# Amplifier_3.net
KiCad netlist of a schematic drawn in Altium Designer
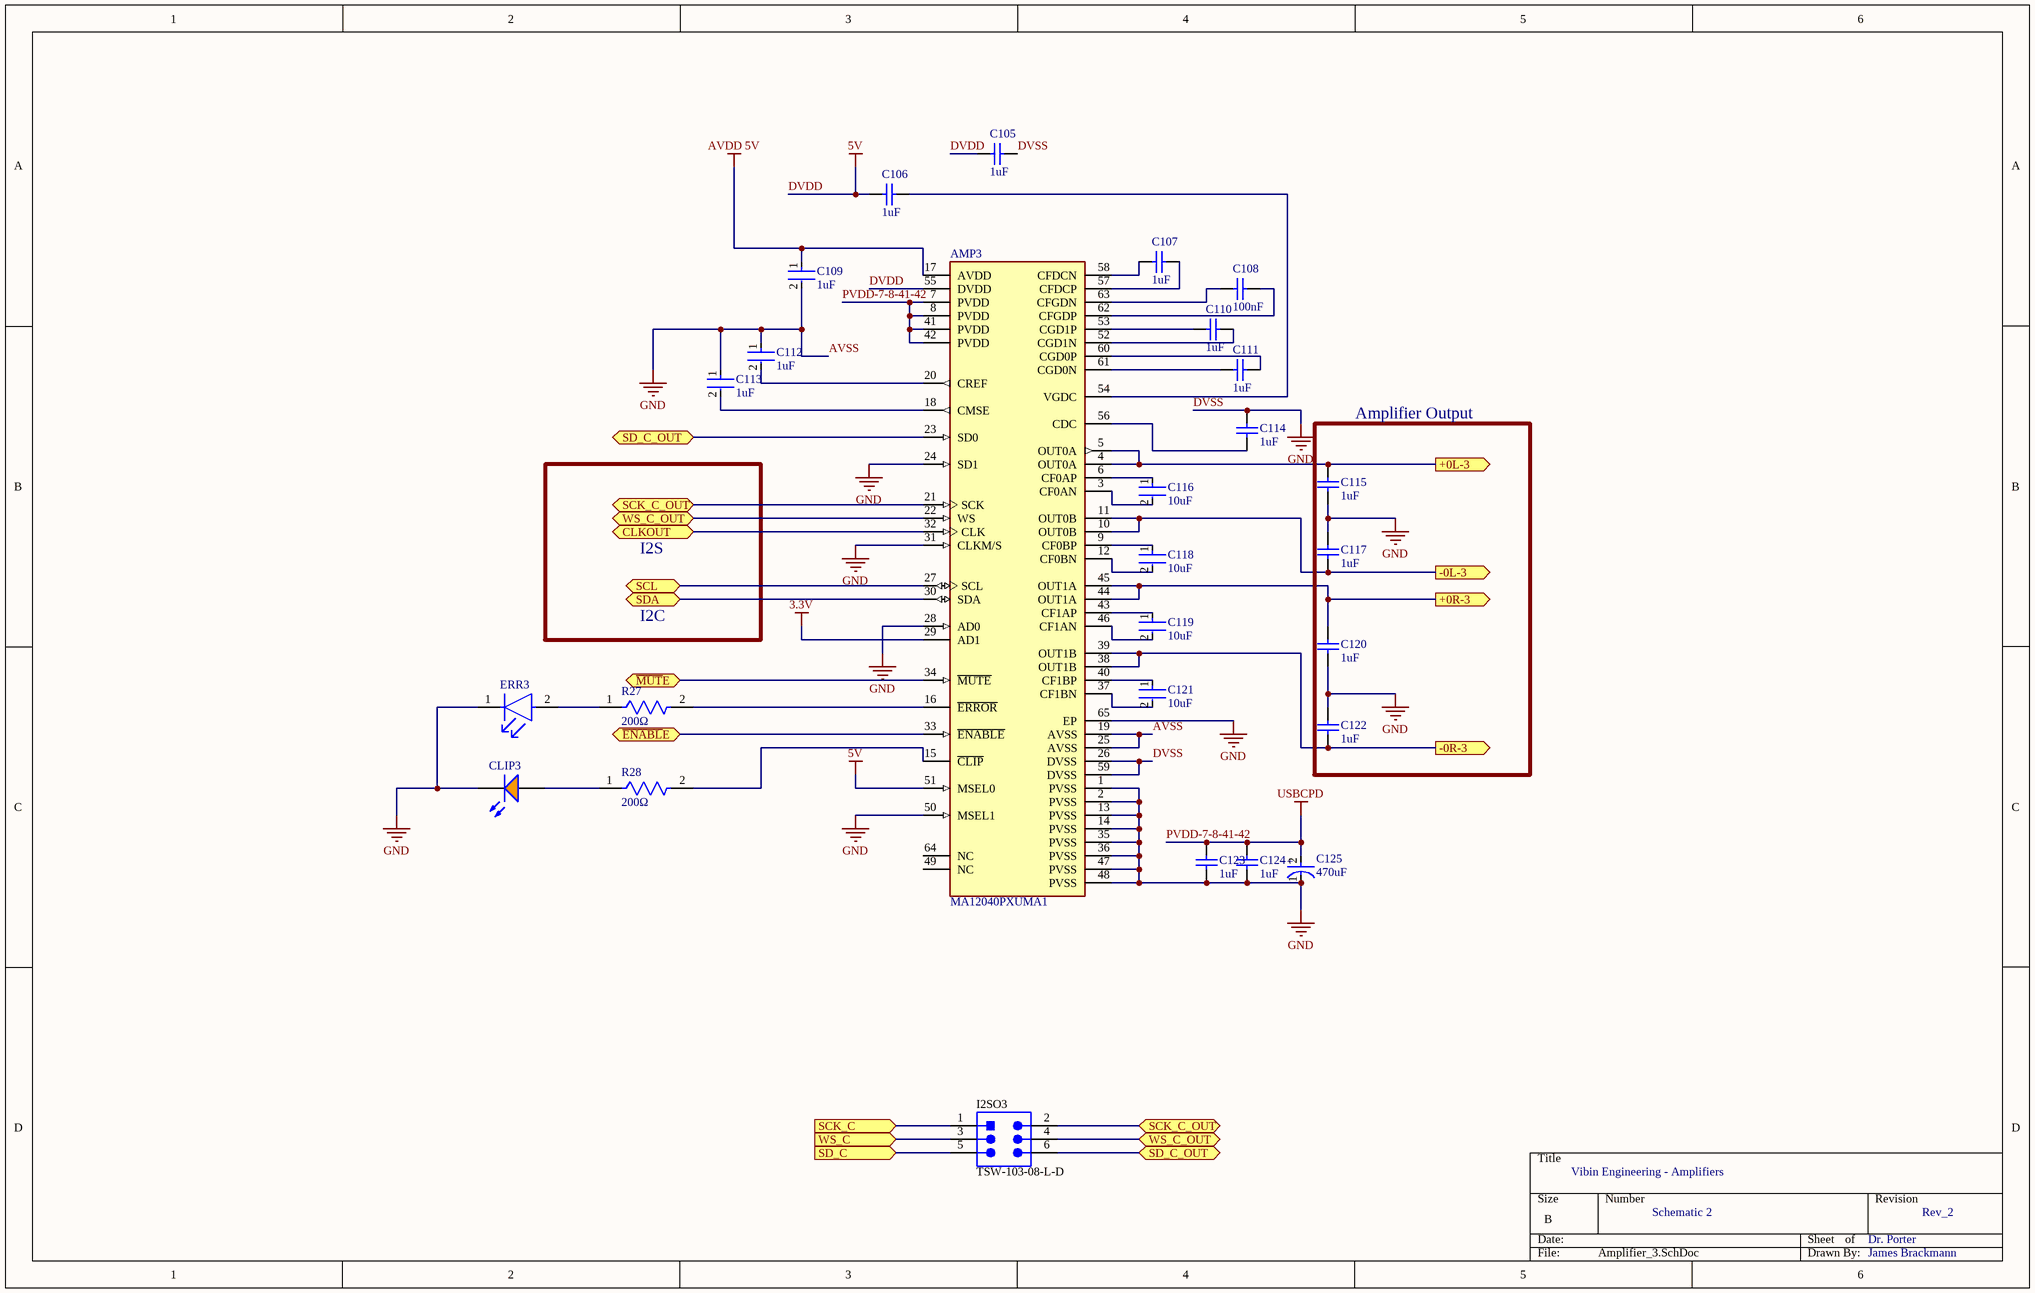
[diagram p0: Amplifier_3.SchDoc]

(export (version "E")
  (design (tool "Eeschema 10.0.6"))
  (components
    (comp (ref "AMP3")
      (value "MA12040PXUMA1")
      (footprint "FP-PG-VQFN-64-IPC_B")
      (description "IC AMP CLASS D STEREO 40W 64QFN")
      (fields
        (field (name "MANUFACTURER") "Infineon")
        (field (name "OCTOPART") "https://octopart.com/ma12040pxuma1-infineon-95984592")
      )
      (libsource (lib "Altium Content Vault") (part "7beef1d240aa861170d3bde7275adf3"))
    )
    (comp (ref "C105")
      (value "1uF")
      (footprint "CAPC1608X90X35LL15T15")
      (description "C0603C105K4RACTU")
      (fields (field (name "MANUFACTURER") "Kemet"))
      (libsource (lib "Altium Content Vault") (part "CAP"))
    )
    (comp (ref "C106")
      (value "1uF")
      (footprint "CAPC1608X90X35LL15T15")
      (description "C0603C105K4RACTU")
      (fields (field (name "MANUFACTURER") "Kemet"))
      (libsource (lib "Altium Content Vault") (part "CAP"))
    )
    (comp (ref "C107")
      (value "1uF")
      (footprint "CAPC1608X90X35LL15T15")
      (description "C0603C105K4RACTU")
      (fields (field (name "MANUFACTURER") "Kemet"))
      (libsource (lib "Altium Content Vault") (part "CAP"))
    )
    (comp (ref "C108")
      (value "100nF")
      (footprint "CAPC1608X90X35ML10T15")
      (fields
        (field (name "TOLERANCE") "10%")
        (field (name "VOLTAGE") "50V")
        (field (name "MANUFACTURER") "Murata")
      )
      (libsource (lib "Altium Content Vault") (part "CAP-NP-2"))
    )
    (comp (ref "C109")
      (value "1uF")
      (footprint "FP-GRM15-0_1-MFG")
      (description "CAP CER 1UF 10V X5R 0402         GRM155R61A105KE15D")
      (fields
        (field (name "OCTOPART") "https://octopart.com/grm155r61a105ke15d-murata-197442")
        (field (name "MANUFACTURER PART NUMBER") "GRM155R61A105KE15D")
      )
      (libsource (lib "Altium Content Vault") (part "02cd4be3c70576c341d710602a673aa"))
    )
    (comp (ref "C110")
      (value "1uF")
      (footprint "CAPC1608X90X35LL15T15")
      (description "C0603C105K4RACTU")
      (fields (field (name "MANUFACTURER") "Kemet"))
      (libsource (lib "Altium Content Vault") (part "CAP"))
    )
    (comp (ref "C111")
      (value "1uF")
      (footprint "CAPC1608X90X35LL15T15")
      (description "C0603C105K4RACTU")
      (fields (field (name "MANUFACTURER") "Kemet"))
      (libsource (lib "Altium Content Vault") (part "CAP"))
    )
    (comp (ref "C112")
      (value "1uF")
      (footprint "FP-GRM15-0_1-MFG")
      (description "CAP CER 1UF 10V X5R 0402         GRM155R61A105KE15D")
      (fields
        (field (name "OCTOPART") "https://octopart.com/grm155r61a105ke15d-murata-197442")
        (field (name "MANUFACTURER PART NUMBER") "GRM155R61A105KE15D")
      )
      (libsource (lib "Altium Content Vault") (part "02cd4be3c70576c341d710602a673aa"))
    )
    (comp (ref "C113")
      (value "1uF")
      (footprint "FP-GRM15-0_1-MFG")
      (description "CAP CER 1UF 10V X5R 0402         GRM155R61A105KE15D")
      (fields
        (field (name "OCTOPART") "https://octopart.com/grm155r61a105ke15d-murata-197442")
        (field (name "MANUFACTURER PART NUMBER") "GRM155R61A105KE15D")
      )
      (libsource (lib "Altium Content Vault") (part "02cd4be3c70576c341d710602a673aa"))
    )
    (comp (ref "C114")
      (value "1uF")
      (footprint "CAPC1608X90X35LL15T15")
      (description "C0603C105K4RACTU")
      (fields (field (name "MANUFACTURER") "Kemet"))
      (libsource (lib "Altium Content Vault") (part "CAP"))
    )
    (comp (ref "C115")
      (value "1uF")
      (footprint "CAPC1608X90X35LL15T15")
      (description "C0603C105K4RACTU")
      (fields (field (name "MANUFACTURER") "Kemet"))
      (libsource (lib "Altium Content Vault") (part "CAP"))
    )
    (comp (ref "C116")
      (value "10uF")
      (footprint "FP-1210-L_3_3_0_4-W_2_5_0-MFG")
      (description "General Purpose Ceramic Capacitor, 1210, 10uF, 10%, X5R, 15%, 25V        12103D106KAT2A")
      (fields (field (name "VOLTAGE") "25V") (field (name "TOLERANCE") "10%"))
      (libsource (lib "Altium Content Vault") (part "b4654b650e69147ec39a6b967a45e02"))
    )
    (comp (ref "C117")
      (value "1uF")
      (footprint "CAPC1608X90X35LL15T15")
      (description "C0603C105K4RACTU")
      (fields (field (name "MANUFACTURER") "Kemet"))
      (libsource (lib "Altium Content Vault") (part "CAP"))
    )
    (comp (ref "C118")
      (value "10uF")
      (footprint "FP-1210-L_3_3_0_4-W_2_5_0-MFG")
      (description "General Purpose Ceramic Capacitor, 1210, 10uF, 10%, X5R, 15%, 25V        12103D106KAT2A")
      (fields (field (name "VOLTAGE") "25V") (field (name "TOLERANCE") "10%"))
      (libsource (lib "Altium Content Vault") (part "b4654b650e69147ec39a6b967a45e02"))
    )
    (comp (ref "C119")
      (value "10uF")
      (footprint "FP-1210-L_3_3_0_4-W_2_5_0-MFG")
      (description "General Purpose Ceramic Capacitor, 1210, 10uF, 10%, X5R, 15%, 25V        12103D106KAT2A")
      (fields (field (name "VOLTAGE") "25V") (field (name "TOLERANCE") "10%"))
      (libsource (lib "Altium Content Vault") (part "b4654b650e69147ec39a6b967a45e02"))
    )
    (comp (ref "C120")
      (value "1uF")
      (footprint "CAPC1608X90X35LL15T15")
      (description "C0603C105K4RACTU")
      (fields (field (name "MANUFACTURER") "Kemet"))
      (libsource (lib "Altium Content Vault") (part "CAP"))
    )
    (comp (ref "C121")
      (value "10uF")
      (footprint "FP-1210-L_3_3_0_4-W_2_5_0-MFG")
      (description "General Purpose Ceramic Capacitor, 1210, 10uF, 10%, X5R, 15%, 25V        12103D106KAT2A")
      (fields (field (name "VOLTAGE") "25V") (field (name "TOLERANCE") "10%"))
      (libsource (lib "Altium Content Vault") (part "b4654b650e69147ec39a6b967a45e02"))
    )
    (comp (ref "C122")
      (value "1uF")
      (footprint "CAPC1608X90X35LL15T15")
      (description "C0603C105K4RACTU")
      (fields (field (name "MANUFACTURER") "Kemet"))
      (libsource (lib "Altium Content Vault") (part "CAP"))
    )
    (comp (ref "C123")
      (value "1uF")
      (footprint "CAPC1608X90X35LL15T15")
      (description "C0603C105K4RACTU")
      (fields (field (name "MANUFACTURER") "Kemet"))
      (libsource (lib "Altium Content Vault") (part "CAP"))
    )
    (comp (ref "C124")
      (value "1uF")
      (footprint "CAPC1608X90X35LL15T15")
      (description "C0603C105K4RACTU")
      (fields (field (name "MANUFACTURER") "Kemet"))
      (libsource (lib "Altium Content Vault") (part "CAP"))
    )
    (comp (ref "C125")
      (value "470uF")
      (footprint "FP-OS-CON-SMT-E12-MFG")
      (description "Conductive Polymer Aluminum Solid Capacitors (OS-CON) 470uF ±20% 20V      20SVPK470M")
      (fields (field (name "TOLERANCE") "20%"))
      (libsource (lib "Altium Content Vault") (part "a00bbbee19879c290e62620ae7e47b1"))
    )
    (comp (ref "CLIP3")
      (value "TLMO1100-GS08")
      (footprint "VISH-TLMX1100-2_V")
      (libsource (lib "Altium Content Vault") (part "LED-ORANGE-AK-2"))
    )
    (comp (ref "ERR3")
      (value "LTST-C190GKT")
      (footprint "FP-LTST-C190GKT-MFG")
      (description "LED GREEN CLEAR CHIP SMD       LTST-C190GKT")
      (fields (field (name "VOLTAGE") "2V"))
      (libsource (lib "Altium Content Vault") (part "8706943c75ba83719d021d2fdc84c58"))
    )
    (comp (ref "I2SO3")
      (value "TSW-103-08-L-D")
      (footprint "SMTC-TSW-103-08-L-D_V")
      (fields (field (name "MANUFACTURER") "Samtec"))
      (libsource (lib "Altium Content Vault") (part "CN-2P-M-R6"))
    )
    (comp (ref "R27")
      (value "200Ω")
      (footprint "FP-ERJ2RK-IPC_A")
      (description "RES SMD 200 OHM 1% 1/10W 0402      ERJ-2RKF2000X")
      (fields (field (name "TOLERANCE") "1%"))
      (libsource (lib "Altium Content Vault") (part "1029c3af85768c4190bb7ad29bc67b5"))
    )
    (comp (ref "R28")
      (value "200Ω")
      (footprint "FP-ERJ2RK-IPC_A")
      (description "RES SMD 200 OHM 1% 1/10W 0402    ERJ-2RKF2000X")
      (fields (field (name "TOLERANCE") "1%"))
      (libsource (lib "Altium Content Vault") (part "1029c3af85768c4190bb7ad29bc67b5"))
    )
  )
  (nets
    (net (code "1") (name "/+0L-3") (class "Default")
      (node (ref "AMP3") (pin "4") (pinfunction "OUT0A_4") (pintype "passive"))
      (node (ref "AMP3") (pin "5") (pinfunction "OUT0A_5") (pintype "output"))
      (node (ref "C115") (pin "1") (pinfunction "1_1") (pintype "passive"))
    )
    (net (code "2") (name "/+0R-3") (class "Default")
      (node (ref "AMP3") (pin "44") (pinfunction "OUT1A_44") (pintype "passive"))
      (node (ref "AMP3") (pin "45") (pinfunction "OUT1A_45") (pintype "passive"))
      (node (ref "C120") (pin "1") (pinfunction "1_1") (pintype "passive"))
    )
    (net (code "3") (name "/-0L-3") (class "Default")
      (node (ref "AMP3") (pin "10") (pinfunction "OUT0B_10") (pintype "passive"))
      (node (ref "AMP3") (pin "11") (pinfunction "OUT0B_11") (pintype "passive"))
      (node (ref "C117") (pin "2") (pinfunction "2_2") (pintype "passive"))
    )
    (net (code "4") (name "/-0R-3") (class "Default")
      (node (ref "AMP3") (pin "38") (pinfunction "OUT1B_38") (pintype "passive"))
      (node (ref "AMP3") (pin "39") (pinfunction "OUT1B_39") (pintype "passive"))
      (node (ref "C122") (pin "2") (pinfunction "2_2") (pintype "passive"))
    )
    (net (code "5") (name "/CLKOUT") (class "Default")
      (node (ref "AMP3") (pin "32") (pinfunction "CLK_32") (pintype "input"))
    )
    (net (code "6") (name "/SCK_C") (class "Default")
      (node (ref "I2SO3") (pin "1") (pinfunction "1_1") (pintype "passive"))
    )
    (net (code "7") (name "/SCK_C_OUT") (class "Default")
      (node (ref "AMP3") (pin "21") (pinfunction "SCK_21") (pintype "input"))
      (node (ref "I2SO3") (pin "2") (pinfunction "2_2") (pintype "passive"))
    )
    (net (code "8") (name "/SCL") (class "Default")
      (node (ref "AMP3") (pin "27") (pinfunction "SCL_27") (pintype "bidirectional"))
    )
    (net (code "9") (name "/SDA") (class "Default")
      (node (ref "AMP3") (pin "30") (pinfunction "SDA_30") (pintype "bidirectional"))
    )
    (net (code "10") (name "/SD_C") (class "Default")
      (node (ref "I2SO3") (pin "5") (pinfunction "5_5") (pintype "passive"))
    )
    (net (code "11") (name "/SD_C_OUT") (class "Default")
      (node (ref "AMP3") (pin "23") (pinfunction "SD0_23") (pintype "input"))
      (node (ref "I2SO3") (pin "6") (pinfunction "6_6") (pintype "passive"))
    )
    (net (code "12") (name "/WS_C") (class "Default")
      (node (ref "I2SO3") (pin "3") (pinfunction "3_3") (pintype "passive"))
    )
    (net (code "13") (name "/WS_C_OUT") (class "Default")
      (node (ref "AMP3") (pin "22") (pinfunction "WS_22") (pintype "input"))
      (node (ref "I2SO3") (pin "4") (pinfunction "4_4") (pintype "passive"))
    )
    (net (code "14") (name "/~{ENABL}E") (class "Default")
      (node (ref "AMP3") (pin "33") (pinfunction "~{ENABLE}_33") (pintype "input"))
    )
    (net (code "15") (name "/~{MUT}E") (class "Default")
      (node (ref "AMP3") (pin "34") (pinfunction "~{MUTE}_34") (pintype "input"))
    )
    (net (code "16") (name "3.3V") (class "Default")
      (node (ref "AMP3") (pin "29") (pinfunction "AD1_29") (pintype "passive"))
    )
    (net (code "17") (name "5V") (class "Default")
      (node (ref "AMP3") (pin "51") (pinfunction "MSEL0_51") (pintype "input"))
      (node (ref "AMP3") (pin "55") (pinfunction "DVDD_55") (pintype "power_in"))
      (node (ref "C105") (pin "2") (pinfunction "2_2") (pintype "passive"))
      (node (ref "C106") (pin "1") (pinfunction "1_1") (pintype "passive"))
    )
    (net (code "18") (name "AVDD 5V") (class "Default")
      (node (ref "AMP3") (pin "17") (pinfunction "AVDD_17") (pintype "power_in"))
      (node (ref "C109") (pin "1") (pinfunction "1_1") (pintype "passive"))
    )
    (net (code "19") (name "GND") (class "Default")
      (node (ref "AMP3") (pin "1") (pinfunction "PVSS_1") (pintype "power_in"))
      (node (ref "AMP3") (pin "13") (pinfunction "PVSS_13") (pintype "power_in"))
      (node (ref "AMP3") (pin "14") (pinfunction "PVSS_14") (pintype "power_in"))
      (node (ref "AMP3") (pin "19") (pinfunction "AVSS_19") (pintype "power_in"))
      (node (ref "AMP3") (pin "2") (pinfunction "PVSS_2") (pintype "power_in"))
      (node (ref "AMP3") (pin "24") (pinfunction "SD1_24") (pintype "input"))
      (node (ref "AMP3") (pin "25") (pinfunction "AVSS_25") (pintype "power_in"))
      (node (ref "AMP3") (pin "26") (pinfunction "DVSS_26") (pintype "power_in"))
      (node (ref "AMP3") (pin "28") (pinfunction "AD0_28") (pintype "input"))
      (node (ref "AMP3") (pin "31") (pinfunction "CLKM/S_31") (pintype "input"))
      (node (ref "AMP3") (pin "35") (pinfunction "PVSS_35") (pintype "power_in"))
      (node (ref "AMP3") (pin "36") (pinfunction "PVSS_36") (pintype "power_in"))
      (node (ref "AMP3") (pin "47") (pinfunction "PVSS_47") (pintype "power_in"))
      (node (ref "AMP3") (pin "48") (pinfunction "PVSS_48") (pintype "power_in"))
      (node (ref "AMP3") (pin "50") (pinfunction "MSEL1_50") (pintype "input"))
      (node (ref "AMP3") (pin "59") (pinfunction "DVSS_59") (pintype "power_in"))
      (node (ref "AMP3") (pin "65") (pinfunction "EP_65") (pintype "power_in"))
      (node (ref "C105") (pin "1") (pinfunction "1_1") (pintype "passive"))
      (node (ref "C109") (pin "2") (pinfunction "2_2") (pintype "passive"))
      (node (ref "C112") (pin "1") (pinfunction "1_1") (pintype "passive"))
      (node (ref "C113") (pin "1") (pinfunction "1_1") (pintype "passive"))
      (node (ref "C114") (pin "1") (pinfunction "1_1") (pintype "passive"))
      (node (ref "C115") (pin "2") (pinfunction "2_2") (pintype "passive"))
      (node (ref "C117") (pin "1") (pinfunction "1_1") (pintype "passive"))
      (node (ref "C120") (pin "2") (pinfunction "2_2") (pintype "passive"))
      (node (ref "C122") (pin "1") (pinfunction "1_1") (pintype "passive"))
      (node (ref "C123") (pin "2") (pinfunction "2_2") (pintype "passive"))
      (node (ref "C124") (pin "2") (pinfunction "2_2") (pintype "passive"))
      (node (ref "C125") (pin "1") (pinfunction "C_1") (pintype "passive"))
      (node (ref "CLIP3") (pin "2") (pinfunction "K_2") (pintype "passive"))
      (node (ref "ERR3") (pin "1") (pinfunction "C_1") (pintype "passive"))
    )
    (net (code "20") (name "Net-(AMP3-CDC)") (class "Default")
      (node (ref "AMP3") (pin "56") (pinfunction "CDC_56") (pintype "passive"))
      (node (ref "C114") (pin "2") (pinfunction "2_2") (pintype "passive"))
    )
    (net (code "21") (name "Net-(AMP3-CF0AN)") (class "Default")
      (node (ref "AMP3") (pin "3") (pinfunction "CF0AN_3") (pintype "passive"))
      (node (ref "C116") (pin "2") (pinfunction "2_2") (pintype "passive"))
    )
    (net (code "22") (name "Net-(AMP3-CF0AP)") (class "Default")
      (node (ref "AMP3") (pin "6") (pinfunction "CF0AP_6") (pintype "passive"))
      (node (ref "C116") (pin "1") (pinfunction "1_1") (pintype "passive"))
    )
    (net (code "23") (name "Net-(AMP3-CF0BN)") (class "Default")
      (node (ref "AMP3") (pin "12") (pinfunction "CF0BN_12") (pintype "passive"))
      (node (ref "C118") (pin "2") (pinfunction "2_2") (pintype "passive"))
    )
    (net (code "24") (name "Net-(AMP3-CF0BP)") (class "Default")
      (node (ref "AMP3") (pin "9") (pinfunction "CF0BP_9") (pintype "passive"))
      (node (ref "C118") (pin "1") (pinfunction "1_1") (pintype "passive"))
    )
    (net (code "25") (name "Net-(AMP3-CF1AN)") (class "Default")
      (node (ref "AMP3") (pin "46") (pinfunction "CF1AN_46") (pintype "passive"))
      (node (ref "C119") (pin "2") (pinfunction "2_2") (pintype "passive"))
    )
    (net (code "26") (name "Net-(AMP3-CF1AP)") (class "Default")
      (node (ref "AMP3") (pin "43") (pinfunction "CF1AP_43") (pintype "passive"))
      (node (ref "C119") (pin "1") (pinfunction "1_1") (pintype "passive"))
    )
    (net (code "27") (name "Net-(AMP3-CF1BN)") (class "Default")
      (node (ref "AMP3") (pin "37") (pinfunction "CF1BN_37") (pintype "passive"))
      (node (ref "C121") (pin "2") (pinfunction "2_2") (pintype "passive"))
    )
    (net (code "28") (name "Net-(AMP3-CF1BP)") (class "Default")
      (node (ref "AMP3") (pin "40") (pinfunction "CF1BP_40") (pintype "passive"))
      (node (ref "C121") (pin "1") (pinfunction "1_1") (pintype "passive"))
    )
    (net (code "29") (name "Net-(AMP3-CFDCN)") (class "Default")
      (node (ref "AMP3") (pin "58") (pinfunction "CFDCN_58") (pintype "passive"))
      (node (ref "C107") (pin "2") (pinfunction "2_2") (pintype "passive"))
    )
    (net (code "30") (name "Net-(AMP3-CFDCP)") (class "Default")
      (node (ref "AMP3") (pin "57") (pinfunction "CFDCP_57") (pintype "passive"))
      (node (ref "C107") (pin "1") (pinfunction "1_1") (pintype "passive"))
    )
    (net (code "31") (name "Net-(AMP3-CFGDN)") (class "Default")
      (node (ref "AMP3") (pin "63") (pinfunction "CFGDN_63") (pintype "passive"))
      (node (ref "C108") (pin "2") (pinfunction "2_2") (pintype "passive"))
    )
    (net (code "32") (name "Net-(AMP3-CFGDP)") (class "Default")
      (node (ref "AMP3") (pin "62") (pinfunction "CFGDP_62") (pintype "passive"))
      (node (ref "C108") (pin "1") (pinfunction "1_1") (pintype "passive"))
    )
    (net (code "33") (name "Net-(AMP3-CGD0N)") (class "Default")
      (node (ref "AMP3") (pin "61") (pinfunction "CGD0N_61") (pintype "passive"))
      (node (ref "C111") (pin "2") (pinfunction "2_2") (pintype "passive"))
    )
    (net (code "34") (name "Net-(AMP3-CGD0P)") (class "Default")
      (node (ref "AMP3") (pin "60") (pinfunction "CGD0P_60") (pintype "passive"))
      (node (ref "C111") (pin "1") (pinfunction "1_1") (pintype "passive"))
    )
    (net (code "35") (name "Net-(AMP3-CGD1N)") (class "Default")
      (node (ref "AMP3") (pin "52") (pinfunction "CGD1N_52") (pintype "passive"))
      (node (ref "C110") (pin "1") (pinfunction "1_1") (pintype "passive"))
    )
    (net (code "36") (name "Net-(AMP3-CGD1P)") (class "Default")
      (node (ref "AMP3") (pin "53") (pinfunction "CGD1P_53") (pintype "passive"))
      (node (ref "C110") (pin "2") (pinfunction "2_2") (pintype "passive"))
    )
    (net (code "37") (name "Net-(AMP3-CMSE)") (class "Default")
      (node (ref "AMP3") (pin "18") (pinfunction "CMSE_18") (pintype "output"))
      (node (ref "C113") (pin "2") (pinfunction "2_2") (pintype "passive"))
    )
    (net (code "38") (name "Net-(AMP3-CREF)") (class "Default")
      (node (ref "AMP3") (pin "20") (pinfunction "CREF_20") (pintype "output"))
      (node (ref "C112") (pin "2") (pinfunction "2_2") (pintype "passive"))
    )
    (net (code "39") (name "Net-(AMP3-VGDC)") (class "Default")
      (node (ref "AMP3") (pin "54") (pinfunction "VGDC_54") (pintype "power_in"))
      (node (ref "C106") (pin "2") (pinfunction "2_2") (pintype "passive"))
    )
    (net (code "40") (name "Net-(AMP3-~{CLIP})") (class "Default")
      (node (ref "AMP3") (pin "15") (pinfunction "~{CLIP}_15") (pintype "open_collector"))
      (node (ref "R28") (pin "2") (pinfunction "2_2") (pintype "passive"))
    )
    (net (code "41") (name "Net-(AMP3-~{ERROR})") (class "Default")
      (node (ref "AMP3") (pin "16") (pinfunction "~{ERROR}_16") (pintype "open_collector"))
      (node (ref "R27") (pin "2") (pinfunction "2_2") (pintype "passive"))
    )
    (net (code "42") (name "Net-(CLIP3-A)") (class "Default")
      (node (ref "CLIP3") (pin "1") (pinfunction "A_1") (pintype "passive"))
      (node (ref "R28") (pin "1") (pinfunction "1_1") (pintype "passive"))
    )
    (net (code "43") (name "Net-(ERR3-A)") (class "Default")
      (node (ref "ERR3") (pin "2") (pinfunction "A_2") (pintype "passive"))
      (node (ref "R27") (pin "1") (pinfunction "1_1") (pintype "passive"))
    )
    (net (code "44") (name "USBCPD") (class "Default")
      (node (ref "AMP3") (pin "41") (pinfunction "PVDD_41") (pintype "power_in"))
      (node (ref "AMP3") (pin "42") (pinfunction "PVDD_42") (pintype "power_in"))
      (node (ref "AMP3") (pin "7") (pinfunction "PVDD_7") (pintype "power_in"))
      (node (ref "AMP3") (pin "8") (pinfunction "PVDD_8") (pintype "power_in"))
      (node (ref "C123") (pin "1") (pinfunction "1_1") (pintype "passive"))
      (node (ref "C124") (pin "1") (pinfunction "1_1") (pintype "passive"))
      (node (ref "C125") (pin "2") (pinfunction "A_2") (pintype "passive"))
    )
    (net (code "45") (name "unconnected-(AMP3-NC-Pad49)") (class "Default")
      (node (ref "AMP3") (pin "49") (pinfunction "NC_49") (pintype "passive"))
    )
    (net (code "46") (name "unconnected-(AMP3-NC-Pad64)") (class "Default")
      (node (ref "AMP3") (pin "64") (pinfunction "NC_64") (pintype "passive"))
    )
  )
)
